# Modulo_Adaptador.net
KiCad netlist of a schematic drawn in Altium Designer
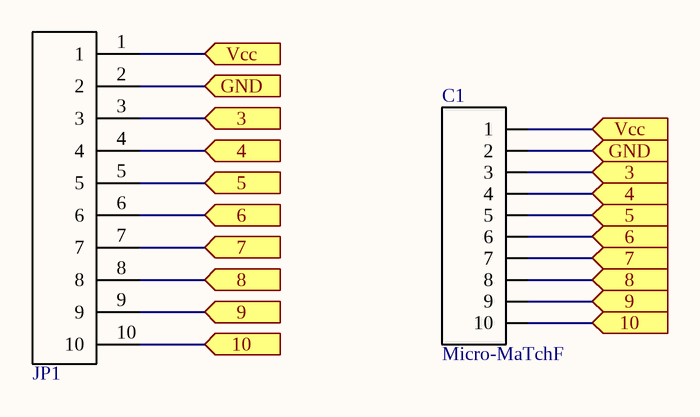
[diagram p0: Modulo_Adaptador.SchDoc]

(export (version "E")
  (design (tool "Eeschema 10.0.6"))
  (components
    (comp (ref "C1")
      (value "Micro-MaTchF")
      (footprint "Micro-MaTch Famale 1.27mm/ Hole")
      (description "Micro-MaTch Famale 1.27mm T/Hole")
      (libsource (lib "Libreria_Borxo_Sch") (part "Micro-MaTchF"))
    )
    (comp (ref "JP1")
      (value "Pines (10X2.54)")
      (footprint "Pin(10X2.54mm)")
      (libsource (lib "Libreria_Borxo_Sch") (part "Pines (10X2.54)"))
    )
  )
  (nets
    (net (code "1") (name "/3") (class "Default")
      (node (ref "C1") (pin "3") (pinfunction "3_3") (pintype "passive"))
      (node (ref "JP1") (pin "3") (pinfunction "3_3") (pintype "passive"))
    )
    (net (code "2") (name "/4") (class "Default")
      (node (ref "C1") (pin "4") (pinfunction "4_4") (pintype "passive"))
      (node (ref "JP1") (pin "4") (pinfunction "4_4") (pintype "passive"))
    )
    (net (code "3") (name "/5") (class "Default")
      (node (ref "C1") (pin "5") (pinfunction "5_5") (pintype "passive"))
      (node (ref "JP1") (pin "5") (pinfunction "5_5") (pintype "passive"))
    )
    (net (code "4") (name "/6") (class "Default")
      (node (ref "C1") (pin "6") (pinfunction "6_6") (pintype "passive"))
      (node (ref "JP1") (pin "6") (pinfunction "6_6") (pintype "passive"))
    )
    (net (code "5") (name "/7") (class "Default")
      (node (ref "C1") (pin "7") (pinfunction "7_7") (pintype "passive"))
      (node (ref "JP1") (pin "7") (pinfunction "7_7") (pintype "passive"))
    )
    (net (code "6") (name "/8") (class "Default")
      (node (ref "C1") (pin "8") (pinfunction "8_8") (pintype "passive"))
      (node (ref "JP1") (pin "8") (pinfunction "8_8") (pintype "passive"))
    )
    (net (code "7") (name "/9") (class "Default")
      (node (ref "C1") (pin "9") (pinfunction "9_9") (pintype "passive"))
      (node (ref "JP1") (pin "9") (pinfunction "9_9") (pintype "passive"))
    )
    (net (code "8") (name "/10") (class "Default")
      (node (ref "C1") (pin "10") (pinfunction "10_10") (pintype "passive"))
      (node (ref "JP1") (pin "10") (pinfunction "10_10") (pintype "passive"))
    )
    (net (code "9") (name "/GND") (class "Default")
      (node (ref "C1") (pin "2") (pinfunction "2_2") (pintype "passive"))
      (node (ref "JP1") (pin "2") (pinfunction "2_2") (pintype "passive"))
    )
    (net (code "10") (name "/Vcc") (class "Default")
      (node (ref "C1") (pin "1") (pinfunction "1_1") (pintype "passive"))
      (node (ref "JP1") (pin "1") (pinfunction "1_1") (pintype "passive"))
    )
  )
)
